# CondizionamentoLM311.net
KiCad netlist of a schematic drawn in EAGLE
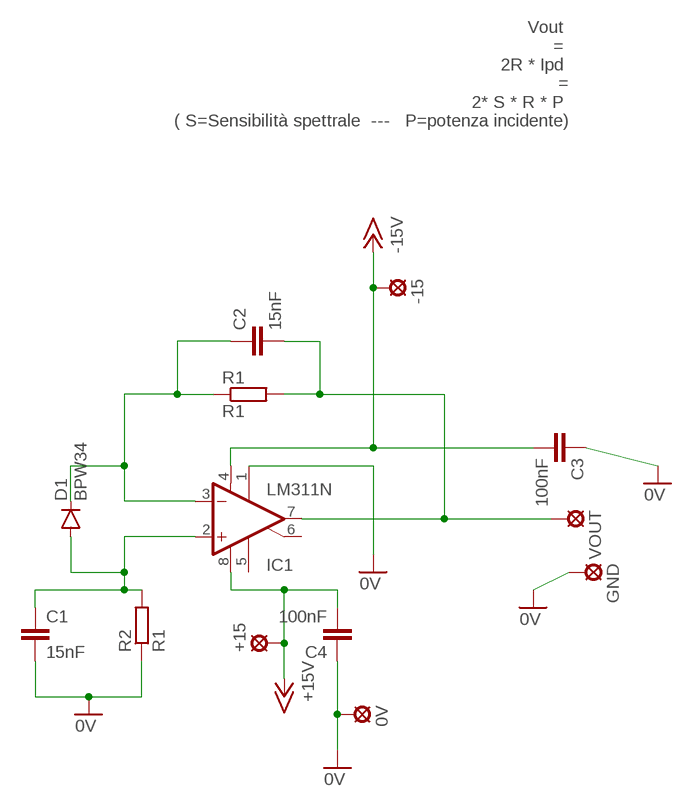
[diagram p0: schematic, sheet 1]

(export (version "E")
  (design (tool "Eeschema 10.0.6"))
  (components
    (comp (ref "+15")
      (value "+15")
      (footprint "eagle-import:LSP10")
      (libsource (lib "eagle-import") (part "LSP10"))
    )
    (comp (ref "-15")
      (value "-15")
      (footprint "eagle-import:LSP10")
      (libsource (lib "eagle-import") (part "LSP10"))
    )
    (comp (ref "0V")
      (value "0V")
      (footprint "eagle-import:LSP10")
      (libsource (lib "eagle-import") (part "LSP10"))
    )
    (comp (ref "C1")
      (value "15nF")
      (footprint "eagle-import:C050-024X044")
      (libsource (lib "eagle-import") (part "C-EU050-024X044"))
    )
    (comp (ref "C2")
      (value "15nF")
      (footprint "eagle-import:C050-024X044")
      (libsource (lib "eagle-import") (part "C-EU050-024X044"))
    )
    (comp (ref "C3")
      (value "100nF")
      (footprint "eagle-import:C050-024X044")
      (libsource (lib "eagle-import") (part "C-EU050-024X044"))
    )
    (comp (ref "C4")
      (value "100nF")
      (footprint "eagle-import:C050-024X044")
      (libsource (lib "eagle-import") (part "C-EU050-024X044"))
    )
    (comp (ref "D1")
      (value "BPW34")
      (footprint "eagle-import:BPW34")
      (libsource (lib "eagle-import") (part "BPW34"))
    )
    (comp (ref "GND")
      (value "0V")
      (footprint "eagle-import:LSP10")
      (libsource (lib "eagle-import") (part "LSP10"))
    )
    (comp (ref "IC1")
      (value "LM311N")
      (footprint "eagle-import:DIL08")
      (libsource (lib "eagle-import") (part "LM311N"))
    )
    (comp (ref "R1")
      (value "R1")
      (footprint "eagle-import:0207_10")
      (libsource (lib "eagle-import") (part "R-EU_0207/10"))
    )
    (comp (ref "R2")
      (value "R1")
      (footprint "eagle-import:0207_10")
      (libsource (lib "eagle-import") (part "R-EU_0207/10"))
    )
    (comp (ref "VOUT")
      (value "Vout")
      (footprint "eagle-import:LSP10")
      (libsource (lib "eagle-import") (part "LSP10"))
    )
  )
  (nets
    (net (code "1") (name "+15V") (class "Default")
      (node (ref "+15") (pin "MP") (pinfunction "MP_MP") (pintype "passive"))
      (node (ref "C4") (pin "2") (pinfunction "2_2") (pintype "passive"))
      (node (ref "IC1") (pin "8") (pinfunction "V+_8") (pintype "power_in"))
    )
    (net (code "2") (name "-15V") (class "Default")
      (node (ref "-15") (pin "MP") (pinfunction "MP_MP") (pintype "passive"))
      (node (ref "C3") (pin "2") (pinfunction "2_2") (pintype "passive"))
      (node (ref "IC1") (pin "4") (pinfunction "V-_4") (pintype "power_in"))
    )
    (net (code "3") (name "0V") (class "Default")
      (node (ref "0V") (pin "MP") (pinfunction "MP_MP") (pintype "passive"))
      (node (ref "C1") (pin "2") (pinfunction "2_2") (pintype "passive"))
      (node (ref "C3") (pin "1") (pinfunction "1_1") (pintype "passive"))
      (node (ref "C4") (pin "1") (pinfunction "1_1") (pintype "passive"))
      (node (ref "GND") (pin "MP") (pinfunction "MP_MP") (pintype "passive"))
      (node (ref "IC1") (pin "1") (pinfunction "GND_1") (pintype "passive"))
      (node (ref "R2") (pin "1") (pinfunction "1_1") (pintype "passive"))
    )
    (net (code "4") (name "Net-(D1-A)") (class "Default")
      (node (ref "C1") (pin "1") (pinfunction "1_1") (pintype "passive"))
      (node (ref "D1") (pin "P$1") (pinfunction "A_P$1") (pintype "passive"))
      (node (ref "IC1") (pin "2") (pinfunction "+IN_2") (pintype "input"))
      (node (ref "R2") (pin "2") (pinfunction "2_2") (pintype "passive"))
    )
    (net (code "5") (name "Net-(D1-C)") (class "Default")
      (node (ref "C2") (pin "1") (pinfunction "1_1") (pintype "passive"))
      (node (ref "D1") (pin "P$2") (pinfunction "C_P$2") (pintype "passive"))
      (node (ref "IC1") (pin "3") (pinfunction "-IN_3") (pintype "input"))
      (node (ref "R1") (pin "1") (pinfunction "1_1") (pintype "passive"))
    )
    (net (code "6") (name "Net-(IC1-OUT)") (class "Default")
      (node (ref "C2") (pin "2") (pinfunction "2_2") (pintype "passive"))
      (node (ref "IC1") (pin "7") (pinfunction "OUT_7") (pintype "output"))
      (node (ref "R1") (pin "2") (pinfunction "2_2") (pintype "passive"))
      (node (ref "VOUT") (pin "MP") (pinfunction "MP_MP") (pintype "passive"))
    )
    (net (code "7") (name "unconnected-(IC1-ON-Pad5)") (class "Default")
      (node (ref "IC1") (pin "5") (pinfunction "ON_5") (pintype "passive"))
    )
    (net (code "8") (name "unconnected-(IC1-ON{slash}STR-Pad6)") (class "Default")
      (node (ref "IC1") (pin "6") (pinfunction "ON/STR_6") (pintype "passive"))
    )
  )
)
